# haystack_nano.net
KiCad netlist of a schematic drawn in EAGLE
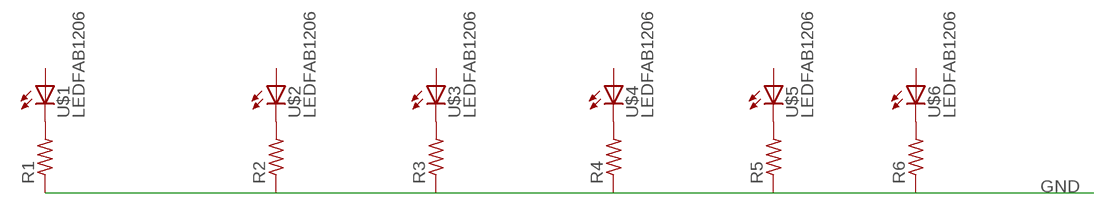
[diagram p0: schematic, sheet 1]

(export (version "E")
  (design (tool "Eeschema 10.0.6"))
  (components
    (comp (ref "R1")
      (value "RES-US1206")
      (footprint "eagle-import:R1206")
      (libsource (lib "eagle-import") (part "RES-US1206"))
    )
    (comp (ref "R2")
      (value "RES-US1206")
      (footprint "eagle-import:R1206")
      (libsource (lib "eagle-import") (part "RES-US1206"))
    )
    (comp (ref "R3")
      (value "RES-US1206")
      (footprint "eagle-import:R1206")
      (libsource (lib "eagle-import") (part "RES-US1206"))
    )
    (comp (ref "R4")
      (value "RES-US1206")
      (footprint "eagle-import:R1206")
      (libsource (lib "eagle-import") (part "RES-US1206"))
    )
    (comp (ref "R5")
      (value "RES-US1206")
      (footprint "eagle-import:R1206")
      (libsource (lib "eagle-import") (part "RES-US1206"))
    )
    (comp (ref "R6")
      (value "RES-US1206")
      (footprint "eagle-import:R1206")
      (libsource (lib "eagle-import") (part "RES-US1206"))
    )
    (comp (ref "U$1")
      (value "LEDFAB1206")
      (footprint "eagle-import:LED1206FAB")
      (libsource (lib "eagle-import") (part "LEDFAB1206"))
    )
    (comp (ref "U$2")
      (value "LEDFAB1206")
      (footprint "eagle-import:LED1206FAB")
      (libsource (lib "eagle-import") (part "LEDFAB1206"))
    )
    (comp (ref "U$3")
      (value "LEDFAB1206")
      (footprint "eagle-import:LED1206FAB")
      (libsource (lib "eagle-import") (part "LEDFAB1206"))
    )
    (comp (ref "U$4")
      (value "LEDFAB1206")
      (footprint "eagle-import:LED1206FAB")
      (libsource (lib "eagle-import") (part "LEDFAB1206"))
    )
    (comp (ref "U$5")
      (value "LEDFAB1206")
      (footprint "eagle-import:LED1206FAB")
      (libsource (lib "eagle-import") (part "LEDFAB1206"))
    )
    (comp (ref "U$6")
      (value "LEDFAB1206")
      (footprint "eagle-import:LED1206FAB")
      (libsource (lib "eagle-import") (part "LEDFAB1206"))
    )
  )
  (nets
    (net (code "1") (name "/GND") (class "Default")
      (node (ref "R1") (pin "1") (pinfunction "1_1") (pintype "passive"))
      (node (ref "R2") (pin "1") (pinfunction "1_1") (pintype "passive"))
      (node (ref "R3") (pin "1") (pinfunction "1_1") (pintype "passive"))
      (node (ref "R4") (pin "1") (pinfunction "1_1") (pintype "passive"))
      (node (ref "R5") (pin "1") (pinfunction "1_1") (pintype "passive"))
      (node (ref "R6") (pin "1") (pinfunction "1_1") (pintype "passive"))
    )
    (net (code "2") (name "Net-(U$1-C)") (class "Default")
      (node (ref "R1") (pin "2") (pinfunction "2_2") (pintype "passive"))
      (node (ref "U$1") (pin "2") (pinfunction "C_2") (pintype "passive"))
    )
    (net (code "3") (name "Net-(U$2-C)") (class "Default")
      (node (ref "R2") (pin "2") (pinfunction "2_2") (pintype "passive"))
      (node (ref "U$2") (pin "2") (pinfunction "C_2") (pintype "passive"))
    )
    (net (code "4") (name "Net-(U$3-C)") (class "Default")
      (node (ref "R3") (pin "2") (pinfunction "2_2") (pintype "passive"))
      (node (ref "U$3") (pin "2") (pinfunction "C_2") (pintype "passive"))
    )
    (net (code "5") (name "Net-(U$4-C)") (class "Default")
      (node (ref "R4") (pin "2") (pinfunction "2_2") (pintype "passive"))
      (node (ref "U$4") (pin "2") (pinfunction "C_2") (pintype "passive"))
    )
    (net (code "6") (name "Net-(U$5-C)") (class "Default")
      (node (ref "R5") (pin "2") (pinfunction "2_2") (pintype "passive"))
      (node (ref "U$5") (pin "2") (pinfunction "C_2") (pintype "passive"))
    )
    (net (code "7") (name "Net-(U$6-C)") (class "Default")
      (node (ref "R6") (pin "2") (pinfunction "2_2") (pintype "passive"))
      (node (ref "U$6") (pin "2") (pinfunction "C_2") (pintype "passive"))
    )
    (net (code "8") (name "unconnected-(U$1-A-Pad1)") (class "Default")
      (node (ref "U$1") (pin "1") (pinfunction "A_1") (pintype "passive"))
    )
    (net (code "9") (name "unconnected-(U$2-A-Pad1)") (class "Default")
      (node (ref "U$2") (pin "1") (pinfunction "A_1") (pintype "passive"))
    )
    (net (code "10") (name "unconnected-(U$3-A-Pad1)") (class "Default")
      (node (ref "U$3") (pin "1") (pinfunction "A_1") (pintype "passive"))
    )
    (net (code "11") (name "unconnected-(U$4-A-Pad1)") (class "Default")
      (node (ref "U$4") (pin "1") (pinfunction "A_1") (pintype "passive"))
    )
    (net (code "12") (name "unconnected-(U$5-A-Pad1)") (class "Default")
      (node (ref "U$5") (pin "1") (pinfunction "A_1") (pintype "passive"))
    )
    (net (code "13") (name "unconnected-(U$6-A-Pad1)") (class "Default")
      (node (ref "U$6") (pin "1") (pinfunction "A_1") (pintype "passive"))
    )
  )
)
